# Sheet1.net
KiCad netlist of a schematic drawn in Altium Designer
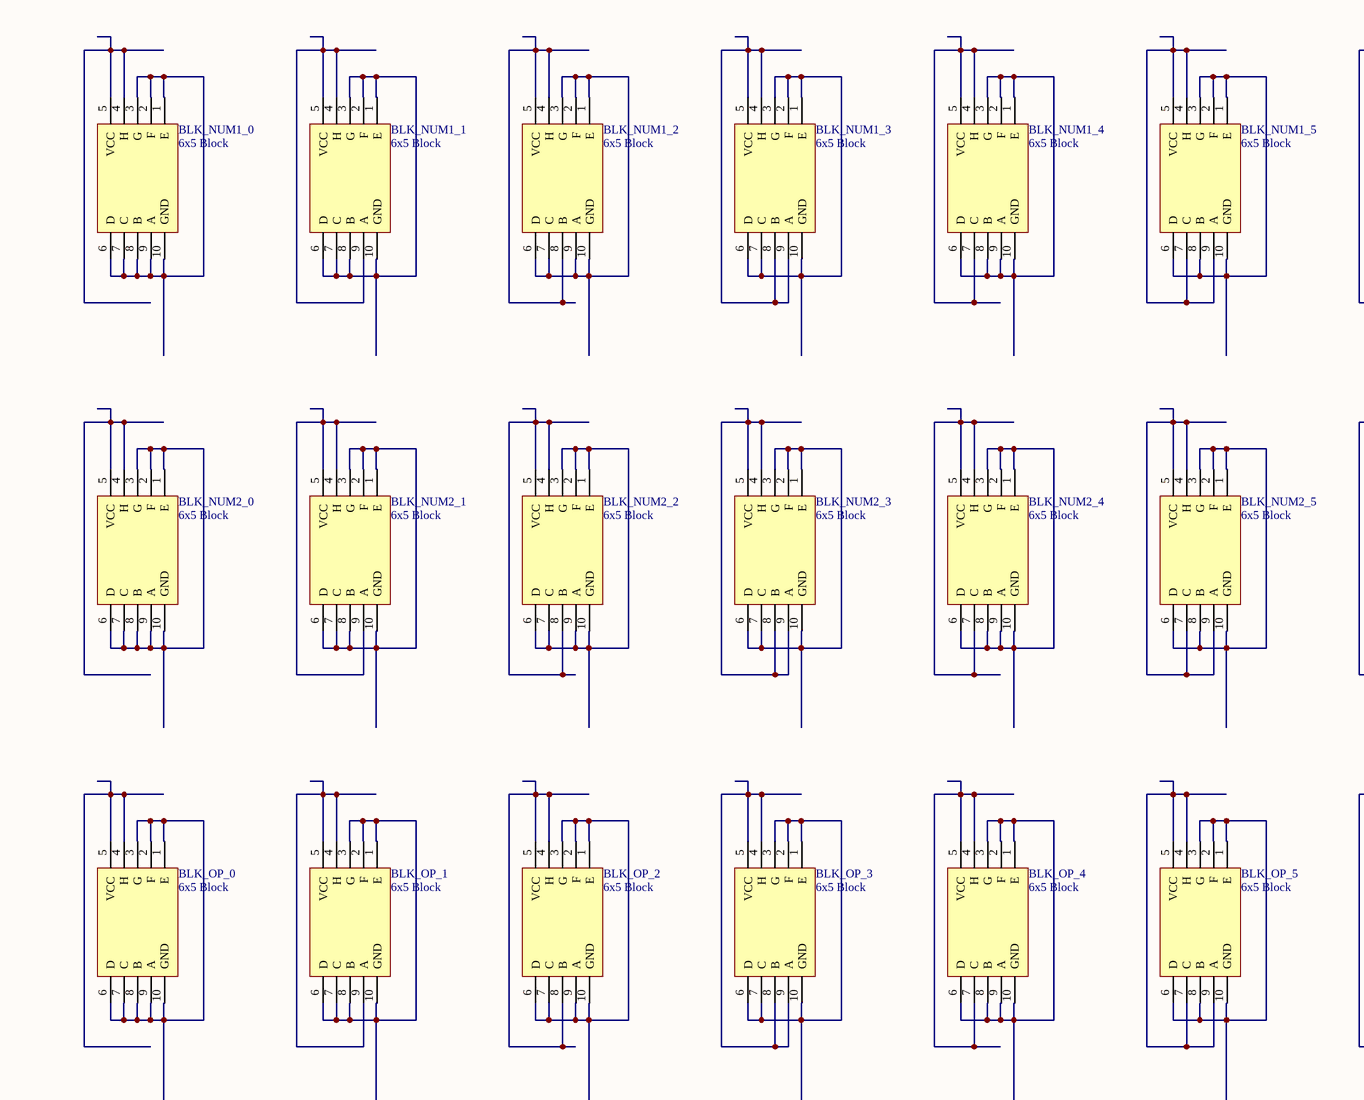
[diagram p0: Sheet1.SchDoc, left]
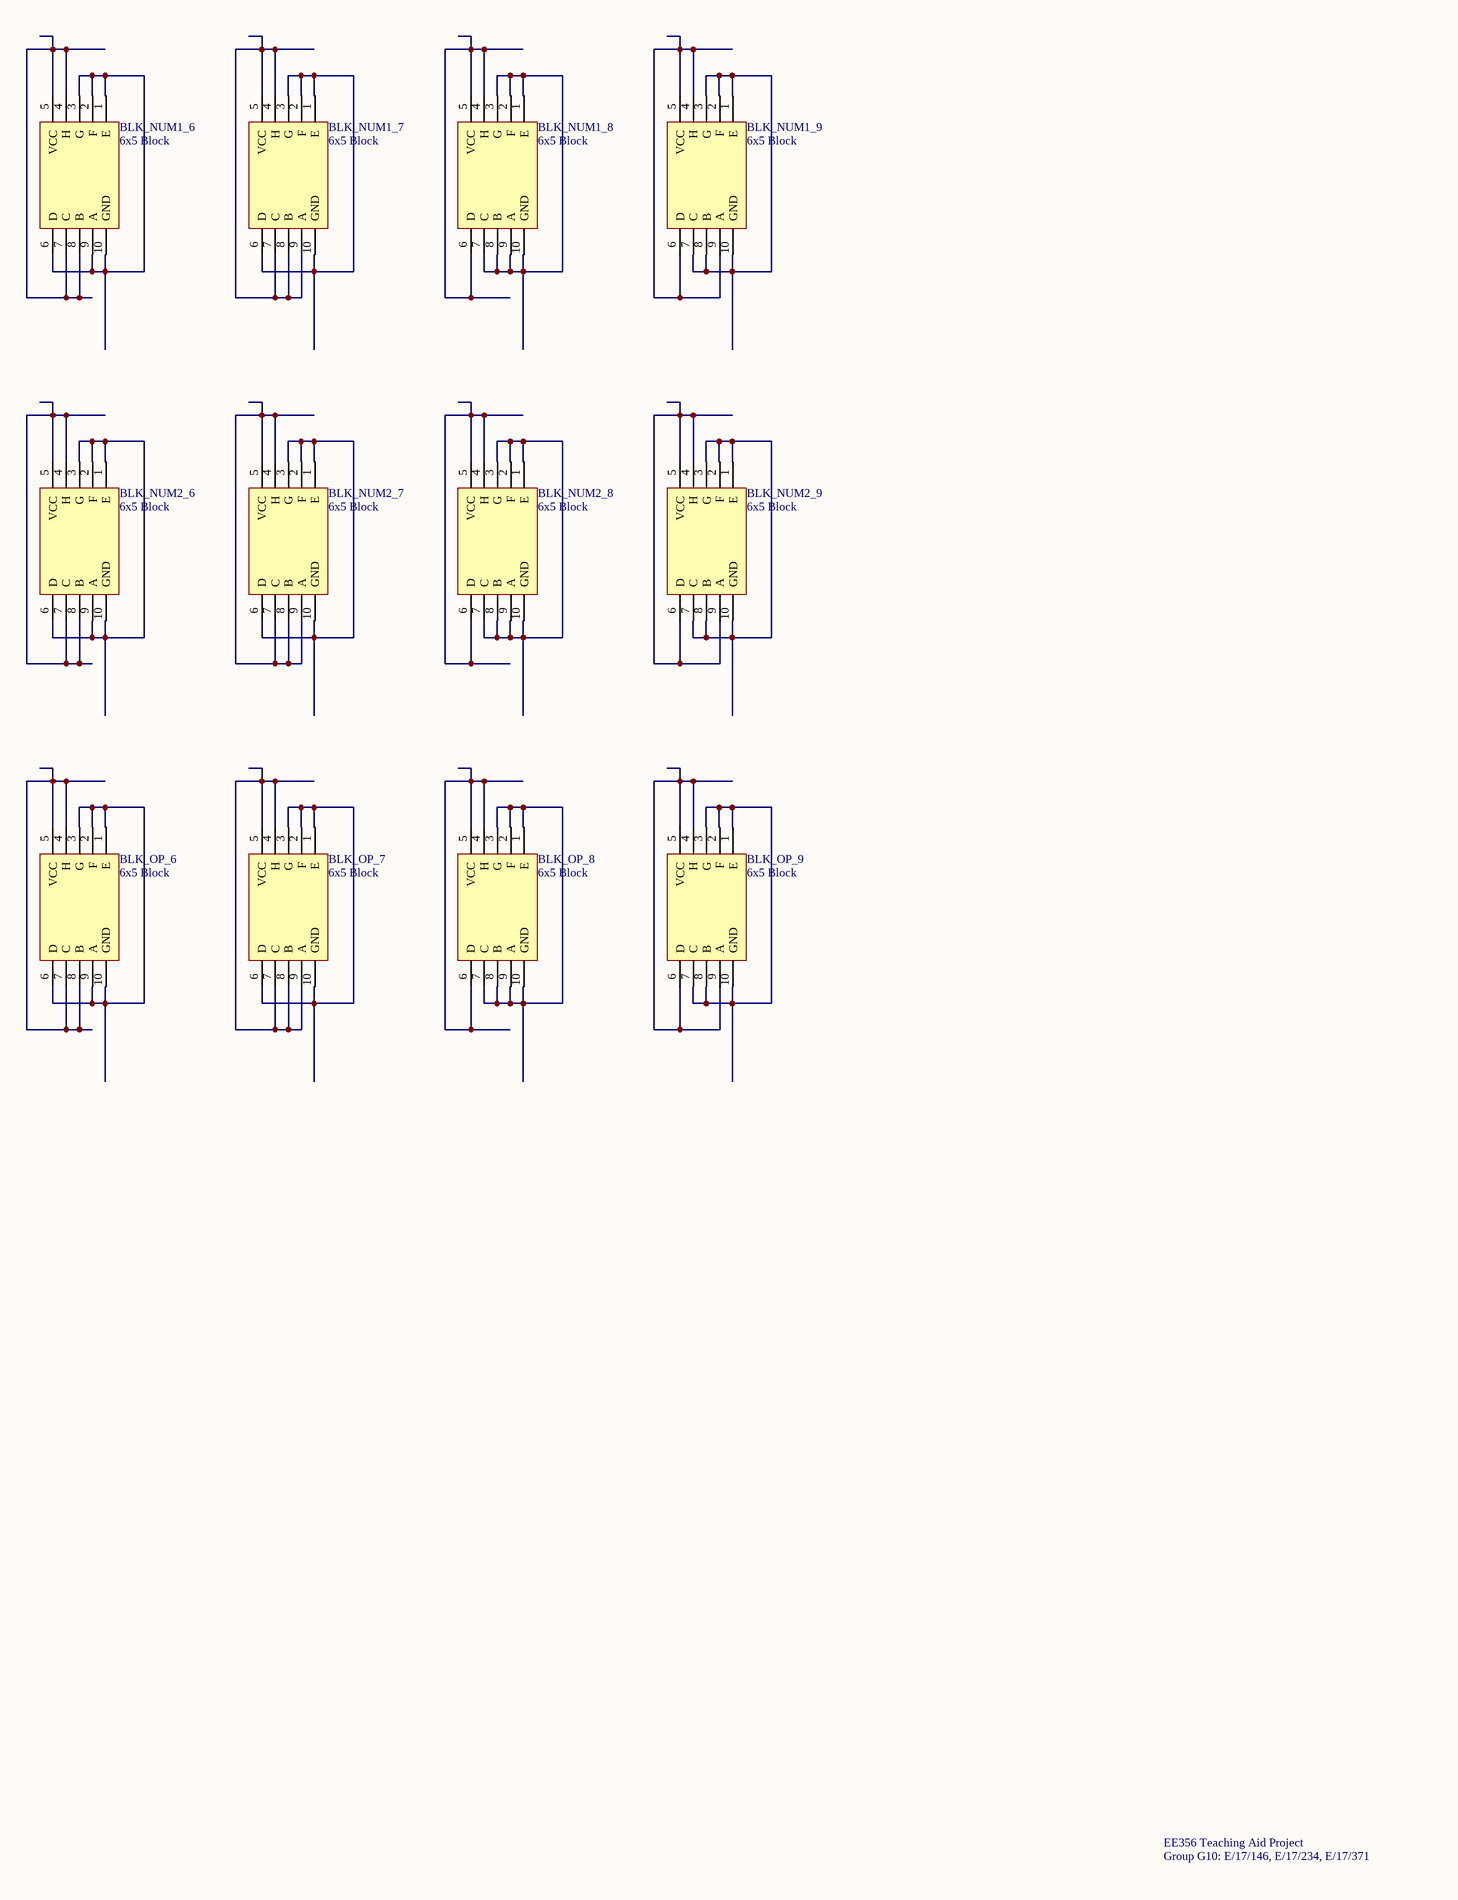
[diagram p1: Sheet1.SchDoc, right]

(export (version "E")
  (design (tool "Eeschema 10.0.6"))
  (components
    (comp (ref "BLK_NUM1_0")
      (value "6x5 Block")
      (footprint "Block_6x5")
      (libsource (lib "Schlib1") (part "Block_6x5"))
    )
    (comp (ref "BLK_NUM1_1")
      (value "6x5 Block")
      (footprint "Block_6x5")
      (libsource (lib "Schlib1") (part "Block_6x5"))
    )
    (comp (ref "BLK_NUM1_2")
      (value "6x5 Block")
      (footprint "Block_6x5")
      (libsource (lib "Schlib1") (part "Block_6x5"))
    )
    (comp (ref "BLK_NUM1_3")
      (value "6x5 Block")
      (footprint "Block_6x5")
      (libsource (lib "Schlib1") (part "Block_6x5"))
    )
    (comp (ref "BLK_NUM1_4")
      (value "6x5 Block")
      (footprint "Block_6x5")
      (libsource (lib "Schlib1") (part "Block_6x5"))
    )
    (comp (ref "BLK_NUM1_5")
      (value "6x5 Block")
      (footprint "Block_6x5")
      (libsource (lib "Schlib1") (part "Block_6x5"))
    )
    (comp (ref "BLK_NUM1_6")
      (value "6x5 Block")
      (footprint "Block_6x5")
      (libsource (lib "Schlib1") (part "Block_6x5"))
    )
    (comp (ref "BLK_NUM1_7")
      (value "6x5 Block")
      (footprint "Block_6x5")
      (libsource (lib "Schlib1") (part "Block_6x5"))
    )
    (comp (ref "BLK_NUM1_8")
      (value "6x5 Block")
      (footprint "Block_6x5")
      (libsource (lib "Schlib1") (part "Block_6x5"))
    )
    (comp (ref "BLK_NUM1_9")
      (value "6x5 Block")
      (footprint "Block_6x5")
      (libsource (lib "Schlib1") (part "Block_6x5"))
    )
    (comp (ref "BLK_NUM2_0")
      (value "6x5 Block")
      (footprint "Block_6x5")
      (libsource (lib "Schlib1") (part "Block_6x5"))
    )
    (comp (ref "BLK_NUM2_1")
      (value "6x5 Block")
      (footprint "Block_6x5")
      (libsource (lib "Schlib1") (part "Block_6x5"))
    )
    (comp (ref "BLK_NUM2_2")
      (value "6x5 Block")
      (footprint "Block_6x5")
      (libsource (lib "Schlib1") (part "Block_6x5"))
    )
    (comp (ref "BLK_NUM2_3")
      (value "6x5 Block")
      (footprint "Block_6x5")
      (libsource (lib "Schlib1") (part "Block_6x5"))
    )
    (comp (ref "BLK_NUM2_4")
      (value "6x5 Block")
      (footprint "Block_6x5")
      (libsource (lib "Schlib1") (part "Block_6x5"))
    )
    (comp (ref "BLK_NUM2_5")
      (value "6x5 Block")
      (footprint "Block_6x5")
      (libsource (lib "Schlib1") (part "Block_6x5"))
    )
    (comp (ref "BLK_NUM2_6")
      (value "6x5 Block")
      (footprint "Block_6x5")
      (libsource (lib "Schlib1") (part "Block_6x5"))
    )
    (comp (ref "BLK_NUM2_7")
      (value "6x5 Block")
      (footprint "Block_6x5")
      (libsource (lib "Schlib1") (part "Block_6x5"))
    )
    (comp (ref "BLK_NUM2_8")
      (value "6x5 Block")
      (footprint "Block_6x5")
      (libsource (lib "Schlib1") (part "Block_6x5"))
    )
    (comp (ref "BLK_NUM2_9")
      (value "6x5 Block")
      (footprint "Block_6x5")
      (libsource (lib "Schlib1") (part "Block_6x5"))
    )
    (comp (ref "BLK_OP_0")
      (value "6x5 Block")
      (footprint "Block_6x5")
      (libsource (lib "Schlib1") (part "Block_6x5"))
    )
    (comp (ref "BLK_OP_1")
      (value "6x5 Block")
      (footprint "Block_6x5")
      (libsource (lib "Schlib1") (part "Block_6x5"))
    )
    (comp (ref "BLK_OP_2")
      (value "6x5 Block")
      (footprint "Block_6x5")
      (libsource (lib "Schlib1") (part "Block_6x5"))
    )
    (comp (ref "BLK_OP_3")
      (value "6x5 Block")
      (footprint "Block_6x5")
      (libsource (lib "Schlib1") (part "Block_6x5"))
    )
    (comp (ref "BLK_OP_4")
      (value "6x5 Block")
      (footprint "Block_6x5")
      (libsource (lib "Schlib1") (part "Block_6x5"))
    )
    (comp (ref "BLK_OP_5")
      (value "6x5 Block")
      (footprint "Block_6x5")
      (libsource (lib "Schlib1") (part "Block_6x5"))
    )
    (comp (ref "BLK_OP_6")
      (value "6x5 Block")
      (footprint "Block_6x5")
      (libsource (lib "Schlib1") (part "Block_6x5"))
    )
    (comp (ref "BLK_OP_7")
      (value "6x5 Block")
      (footprint "Block_6x5")
      (libsource (lib "Schlib1") (part "Block_6x5"))
    )
    (comp (ref "BLK_OP_8")
      (value "6x5 Block")
      (footprint "Block_6x5")
      (libsource (lib "Schlib1") (part "Block_6x5"))
    )
    (comp (ref "BLK_OP_9")
      (value "6x5 Block")
      (footprint "Block_6x5")
      (libsource (lib "Schlib1") (part "Block_6x5"))
    )
  )
  (nets
    (net (code "1") (name "Net-(BLK_NUM1_0-A)") (class "Default")
      (node (ref "BLK_NUM1_0") (pin "1") (pinfunction "E_1") (pintype "passive"))
      (node (ref "BLK_NUM1_0") (pin "10") (pinfunction "GND_10") (pintype "passive"))
      (node (ref "BLK_NUM1_0") (pin "2") (pinfunction "F_2") (pintype "passive"))
      (node (ref "BLK_NUM1_0") (pin "3") (pinfunction "G_3") (pintype "passive"))
      (node (ref "BLK_NUM1_0") (pin "6") (pinfunction "D_6") (pintype "passive"))
      (node (ref "BLK_NUM1_0") (pin "7") (pinfunction "C_7") (pintype "passive"))
      (node (ref "BLK_NUM1_0") (pin "8") (pinfunction "B_8") (pintype "passive"))
      (node (ref "BLK_NUM1_0") (pin "9") (pinfunction "A_9") (pintype "passive"))
    )
    (net (code "2") (name "Net-(BLK_NUM1_0-H)") (class "Default")
      (node (ref "BLK_NUM1_0") (pin "4") (pinfunction "H_4") (pintype "passive"))
      (node (ref "BLK_NUM1_0") (pin "5") (pinfunction "VCC_5") (pintype "passive"))
    )
    (net (code "3") (name "Net-(BLK_NUM1_1-A)") (class "Default")
      (node (ref "BLK_NUM1_1") (pin "4") (pinfunction "H_4") (pintype "passive"))
      (node (ref "BLK_NUM1_1") (pin "5") (pinfunction "VCC_5") (pintype "passive"))
      (node (ref "BLK_NUM1_1") (pin "9") (pinfunction "A_9") (pintype "passive"))
    )
    (net (code "4") (name "Net-(BLK_NUM1_1-B)") (class "Default")
      (node (ref "BLK_NUM1_1") (pin "1") (pinfunction "E_1") (pintype "passive"))
      (node (ref "BLK_NUM1_1") (pin "10") (pinfunction "GND_10") (pintype "passive"))
      (node (ref "BLK_NUM1_1") (pin "2") (pinfunction "F_2") (pintype "passive"))
      (node (ref "BLK_NUM1_1") (pin "3") (pinfunction "G_3") (pintype "passive"))
      (node (ref "BLK_NUM1_1") (pin "6") (pinfunction "D_6") (pintype "passive"))
      (node (ref "BLK_NUM1_1") (pin "7") (pinfunction "C_7") (pintype "passive"))
      (node (ref "BLK_NUM1_1") (pin "8") (pinfunction "B_8") (pintype "passive"))
    )
    (net (code "5") (name "Net-(BLK_NUM1_2-A)") (class "Default")
      (node (ref "BLK_NUM1_2") (pin "1") (pinfunction "E_1") (pintype "passive"))
      (node (ref "BLK_NUM1_2") (pin "10") (pinfunction "GND_10") (pintype "passive"))
      (node (ref "BLK_NUM1_2") (pin "2") (pinfunction "F_2") (pintype "passive"))
      (node (ref "BLK_NUM1_2") (pin "3") (pinfunction "G_3") (pintype "passive"))
      (node (ref "BLK_NUM1_2") (pin "6") (pinfunction "D_6") (pintype "passive"))
      (node (ref "BLK_NUM1_2") (pin "7") (pinfunction "C_7") (pintype "passive"))
      (node (ref "BLK_NUM1_2") (pin "9") (pinfunction "A_9") (pintype "passive"))
    )
    (net (code "6") (name "Net-(BLK_NUM1_2-B)") (class "Default")
      (node (ref "BLK_NUM1_2") (pin "4") (pinfunction "H_4") (pintype "passive"))
      (node (ref "BLK_NUM1_2") (pin "5") (pinfunction "VCC_5") (pintype "passive"))
      (node (ref "BLK_NUM1_2") (pin "8") (pinfunction "B_8") (pintype "passive"))
    )
    (net (code "7") (name "Net-(BLK_NUM1_3-A)") (class "Default")
      (node (ref "BLK_NUM1_3") (pin "4") (pinfunction "H_4") (pintype "passive"))
      (node (ref "BLK_NUM1_3") (pin "5") (pinfunction "VCC_5") (pintype "passive"))
      (node (ref "BLK_NUM1_3") (pin "8") (pinfunction "B_8") (pintype "passive"))
      (node (ref "BLK_NUM1_3") (pin "9") (pinfunction "A_9") (pintype "passive"))
    )
    (net (code "8") (name "Net-(BLK_NUM1_3-C)") (class "Default")
      (node (ref "BLK_NUM1_3") (pin "1") (pinfunction "E_1") (pintype "passive"))
      (node (ref "BLK_NUM1_3") (pin "10") (pinfunction "GND_10") (pintype "passive"))
      (node (ref "BLK_NUM1_3") (pin "2") (pinfunction "F_2") (pintype "passive"))
      (node (ref "BLK_NUM1_3") (pin "3") (pinfunction "G_3") (pintype "passive"))
      (node (ref "BLK_NUM1_3") (pin "6") (pinfunction "D_6") (pintype "passive"))
      (node (ref "BLK_NUM1_3") (pin "7") (pinfunction "C_7") (pintype "passive"))
    )
    (net (code "9") (name "Net-(BLK_NUM1_4-A)") (class "Default")
      (node (ref "BLK_NUM1_4") (pin "1") (pinfunction "E_1") (pintype "passive"))
      (node (ref "BLK_NUM1_4") (pin "10") (pinfunction "GND_10") (pintype "passive"))
      (node (ref "BLK_NUM1_4") (pin "2") (pinfunction "F_2") (pintype "passive"))
      (node (ref "BLK_NUM1_4") (pin "3") (pinfunction "G_3") (pintype "passive"))
      (node (ref "BLK_NUM1_4") (pin "6") (pinfunction "D_6") (pintype "passive"))
      (node (ref "BLK_NUM1_4") (pin "8") (pinfunction "B_8") (pintype "passive"))
      (node (ref "BLK_NUM1_4") (pin "9") (pinfunction "A_9") (pintype "passive"))
    )
    (net (code "10") (name "Net-(BLK_NUM1_4-C)") (class "Default")
      (node (ref "BLK_NUM1_4") (pin "4") (pinfunction "H_4") (pintype "passive"))
      (node (ref "BLK_NUM1_4") (pin "5") (pinfunction "VCC_5") (pintype "passive"))
      (node (ref "BLK_NUM1_4") (pin "7") (pinfunction "C_7") (pintype "passive"))
    )
    (net (code "11") (name "Net-(BLK_NUM1_5-A)") (class "Default")
      (node (ref "BLK_NUM1_5") (pin "4") (pinfunction "H_4") (pintype "passive"))
      (node (ref "BLK_NUM1_5") (pin "5") (pinfunction "VCC_5") (pintype "passive"))
      (node (ref "BLK_NUM1_5") (pin "7") (pinfunction "C_7") (pintype "passive"))
      (node (ref "BLK_NUM1_5") (pin "9") (pinfunction "A_9") (pintype "passive"))
    )
    (net (code "12") (name "Net-(BLK_NUM1_5-B)") (class "Default")
      (node (ref "BLK_NUM1_5") (pin "1") (pinfunction "E_1") (pintype "passive"))
      (node (ref "BLK_NUM1_5") (pin "10") (pinfunction "GND_10") (pintype "passive"))
      (node (ref "BLK_NUM1_5") (pin "2") (pinfunction "F_2") (pintype "passive"))
      (node (ref "BLK_NUM1_5") (pin "3") (pinfunction "G_3") (pintype "passive"))
      (node (ref "BLK_NUM1_5") (pin "6") (pinfunction "D_6") (pintype "passive"))
      (node (ref "BLK_NUM1_5") (pin "8") (pinfunction "B_8") (pintype "passive"))
    )
    (net (code "13") (name "Net-(BLK_NUM1_6-A)") (class "Default")
      (node (ref "BLK_NUM1_6") (pin "1") (pinfunction "E_1") (pintype "passive"))
      (node (ref "BLK_NUM1_6") (pin "10") (pinfunction "GND_10") (pintype "passive"))
      (node (ref "BLK_NUM1_6") (pin "2") (pinfunction "F_2") (pintype "passive"))
      (node (ref "BLK_NUM1_6") (pin "3") (pinfunction "G_3") (pintype "passive"))
      (node (ref "BLK_NUM1_6") (pin "6") (pinfunction "D_6") (pintype "passive"))
      (node (ref "BLK_NUM1_6") (pin "9") (pinfunction "A_9") (pintype "passive"))
    )
    (net (code "14") (name "Net-(BLK_NUM1_6-B)") (class "Default")
      (node (ref "BLK_NUM1_6") (pin "4") (pinfunction "H_4") (pintype "passive"))
      (node (ref "BLK_NUM1_6") (pin "5") (pinfunction "VCC_5") (pintype "passive"))
      (node (ref "BLK_NUM1_6") (pin "7") (pinfunction "C_7") (pintype "passive"))
      (node (ref "BLK_NUM1_6") (pin "8") (pinfunction "B_8") (pintype "passive"))
    )
    (net (code "15") (name "Net-(BLK_NUM1_7-A)") (class "Default")
      (node (ref "BLK_NUM1_7") (pin "4") (pinfunction "H_4") (pintype "passive"))
      (node (ref "BLK_NUM1_7") (pin "5") (pinfunction "VCC_5") (pintype "passive"))
      (node (ref "BLK_NUM1_7") (pin "7") (pinfunction "C_7") (pintype "passive"))
      (node (ref "BLK_NUM1_7") (pin "8") (pinfunction "B_8") (pintype "passive"))
      (node (ref "BLK_NUM1_7") (pin "9") (pinfunction "A_9") (pintype "passive"))
    )
    (net (code "16") (name "Net-(BLK_NUM1_7-D)") (class "Default")
      (node (ref "BLK_NUM1_7") (pin "1") (pinfunction "E_1") (pintype "passive"))
      (node (ref "BLK_NUM1_7") (pin "10") (pinfunction "GND_10") (pintype "passive"))
      (node (ref "BLK_NUM1_7") (pin "2") (pinfunction "F_2") (pintype "passive"))
      (node (ref "BLK_NUM1_7") (pin "3") (pinfunction "G_3") (pintype "passive"))
      (node (ref "BLK_NUM1_7") (pin "6") (pinfunction "D_6") (pintype "passive"))
    )
    (net (code "17") (name "Net-(BLK_NUM1_8-A)") (class "Default")
      (node (ref "BLK_NUM1_8") (pin "1") (pinfunction "E_1") (pintype "passive"))
      (node (ref "BLK_NUM1_8") (pin "10") (pinfunction "GND_10") (pintype "passive"))
      (node (ref "BLK_NUM1_8") (pin "2") (pinfunction "F_2") (pintype "passive"))
      (node (ref "BLK_NUM1_8") (pin "3") (pinfunction "G_3") (pintype "passive"))
      (node (ref "BLK_NUM1_8") (pin "7") (pinfunction "C_7") (pintype "passive"))
      (node (ref "BLK_NUM1_8") (pin "8") (pinfunction "B_8") (pintype "passive"))
      (node (ref "BLK_NUM1_8") (pin "9") (pinfunction "A_9") (pintype "passive"))
    )
    (net (code "18") (name "Net-(BLK_NUM1_8-D)") (class "Default")
      (node (ref "BLK_NUM1_8") (pin "4") (pinfunction "H_4") (pintype "passive"))
      (node (ref "BLK_NUM1_8") (pin "5") (pinfunction "VCC_5") (pintype "passive"))
      (node (ref "BLK_NUM1_8") (pin "6") (pinfunction "D_6") (pintype "passive"))
    )
    (net (code "19") (name "Net-(BLK_NUM1_9-A)") (class "Default")
      (node (ref "BLK_NUM1_9") (pin "4") (pinfunction "H_4") (pintype "passive"))
      (node (ref "BLK_NUM1_9") (pin "5") (pinfunction "VCC_5") (pintype "passive"))
      (node (ref "BLK_NUM1_9") (pin "6") (pinfunction "D_6") (pintype "passive"))
      (node (ref "BLK_NUM1_9") (pin "9") (pinfunction "A_9") (pintype "passive"))
    )
    (net (code "20") (name "Net-(BLK_NUM1_9-B)") (class "Default")
      (node (ref "BLK_NUM1_9") (pin "1") (pinfunction "E_1") (pintype "passive"))
      (node (ref "BLK_NUM1_9") (pin "10") (pinfunction "GND_10") (pintype "passive"))
      (node (ref "BLK_NUM1_9") (pin "2") (pinfunction "F_2") (pintype "passive"))
      (node (ref "BLK_NUM1_9") (pin "3") (pinfunction "G_3") (pintype "passive"))
      (node (ref "BLK_NUM1_9") (pin "7") (pinfunction "C_7") (pintype "passive"))
      (node (ref "BLK_NUM1_9") (pin "8") (pinfunction "B_8") (pintype "passive"))
    )
    (net (code "21") (name "Net-(BLK_NUM2_0-A)") (class "Default")
      (node (ref "BLK_NUM2_0") (pin "1") (pinfunction "E_1") (pintype "passive"))
      (node (ref "BLK_NUM2_0") (pin "10") (pinfunction "GND_10") (pintype "passive"))
      (node (ref "BLK_NUM2_0") (pin "2") (pinfunction "F_2") (pintype "passive"))
      (node (ref "BLK_NUM2_0") (pin "3") (pinfunction "G_3") (pintype "passive"))
      (node (ref "BLK_NUM2_0") (pin "6") (pinfunction "D_6") (pintype "passive"))
      (node (ref "BLK_NUM2_0") (pin "7") (pinfunction "C_7") (pintype "passive"))
      (node (ref "BLK_NUM2_0") (pin "8") (pinfunction "B_8") (pintype "passive"))
      (node (ref "BLK_NUM2_0") (pin "9") (pinfunction "A_9") (pintype "passive"))
    )
    (net (code "22") (name "Net-(BLK_NUM2_0-H)") (class "Default")
      (node (ref "BLK_NUM2_0") (pin "4") (pinfunction "H_4") (pintype "passive"))
      (node (ref "BLK_NUM2_0") (pin "5") (pinfunction "VCC_5") (pintype "passive"))
    )
    (net (code "23") (name "Net-(BLK_NUM2_1-A)") (class "Default")
      (node (ref "BLK_NUM2_1") (pin "4") (pinfunction "H_4") (pintype "passive"))
      (node (ref "BLK_NUM2_1") (pin "5") (pinfunction "VCC_5") (pintype "passive"))
      (node (ref "BLK_NUM2_1") (pin "9") (pinfunction "A_9") (pintype "passive"))
    )
    (net (code "24") (name "Net-(BLK_NUM2_1-B)") (class "Default")
      (node (ref "BLK_NUM2_1") (pin "1") (pinfunction "E_1") (pintype "passive"))
      (node (ref "BLK_NUM2_1") (pin "10") (pinfunction "GND_10") (pintype "passive"))
      (node (ref "BLK_NUM2_1") (pin "2") (pinfunction "F_2") (pintype "passive"))
      (node (ref "BLK_NUM2_1") (pin "3") (pinfunction "G_3") (pintype "passive"))
      (node (ref "BLK_NUM2_1") (pin "6") (pinfunction "D_6") (pintype "passive"))
      (node (ref "BLK_NUM2_1") (pin "7") (pinfunction "C_7") (pintype "passive"))
      (node (ref "BLK_NUM2_1") (pin "8") (pinfunction "B_8") (pintype "passive"))
    )
    (net (code "25") (name "Net-(BLK_NUM2_2-A)") (class "Default")
      (node (ref "BLK_NUM2_2") (pin "1") (pinfunction "E_1") (pintype "passive"))
      (node (ref "BLK_NUM2_2") (pin "10") (pinfunction "GND_10") (pintype "passive"))
      (node (ref "BLK_NUM2_2") (pin "2") (pinfunction "F_2") (pintype "passive"))
      (node (ref "BLK_NUM2_2") (pin "3") (pinfunction "G_3") (pintype "passive"))
      (node (ref "BLK_NUM2_2") (pin "6") (pinfunction "D_6") (pintype "passive"))
      (node (ref "BLK_NUM2_2") (pin "7") (pinfunction "C_7") (pintype "passive"))
      (node (ref "BLK_NUM2_2") (pin "9") (pinfunction "A_9") (pintype "passive"))
    )
    (net (code "26") (name "Net-(BLK_NUM2_2-B)") (class "Default")
      (node (ref "BLK_NUM2_2") (pin "4") (pinfunction "H_4") (pintype "passive"))
      (node (ref "BLK_NUM2_2") (pin "5") (pinfunction "VCC_5") (pintype "passive"))
      (node (ref "BLK_NUM2_2") (pin "8") (pinfunction "B_8") (pintype "passive"))
    )
    (net (code "27") (name "Net-(BLK_NUM2_3-A)") (class "Default")
      (node (ref "BLK_NUM2_3") (pin "4") (pinfunction "H_4") (pintype "passive"))
      (node (ref "BLK_NUM2_3") (pin "5") (pinfunction "VCC_5") (pintype "passive"))
      (node (ref "BLK_NUM2_3") (pin "8") (pinfunction "B_8") (pintype "passive"))
      (node (ref "BLK_NUM2_3") (pin "9") (pinfunction "A_9") (pintype "passive"))
    )
    (net (code "28") (name "Net-(BLK_NUM2_3-C)") (class "Default")
      (node (ref "BLK_NUM2_3") (pin "1") (pinfunction "E_1") (pintype "passive"))
      (node (ref "BLK_NUM2_3") (pin "10") (pinfunction "GND_10") (pintype "passive"))
      (node (ref "BLK_NUM2_3") (pin "2") (pinfunction "F_2") (pintype "passive"))
      (node (ref "BLK_NUM2_3") (pin "3") (pinfunction "G_3") (pintype "passive"))
      (node (ref "BLK_NUM2_3") (pin "6") (pinfunction "D_6") (pintype "passive"))
      (node (ref "BLK_NUM2_3") (pin "7") (pinfunction "C_7") (pintype "passive"))
    )
    (net (code "29") (name "Net-(BLK_NUM2_4-A)") (class "Default")
      (node (ref "BLK_NUM2_4") (pin "1") (pinfunction "E_1") (pintype "passive"))
      (node (ref "BLK_NUM2_4") (pin "10") (pinfunction "GND_10") (pintype "passive"))
      (node (ref "BLK_NUM2_4") (pin "2") (pinfunction "F_2") (pintype "passive"))
      (node (ref "BLK_NUM2_4") (pin "3") (pinfunction "G_3") (pintype "passive"))
      (node (ref "BLK_NUM2_4") (pin "6") (pinfunction "D_6") (pintype "passive"))
      (node (ref "BLK_NUM2_4") (pin "8") (pinfunction "B_8") (pintype "passive"))
      (node (ref "BLK_NUM2_4") (pin "9") (pinfunction "A_9") (pintype "passive"))
    )
    (net (code "30") (name "Net-(BLK_NUM2_4-C)") (class "Default")
      (node (ref "BLK_NUM2_4") (pin "4") (pinfunction "H_4") (pintype "passive"))
      (node (ref "BLK_NUM2_4") (pin "5") (pinfunction "VCC_5") (pintype "passive"))
      (node (ref "BLK_NUM2_4") (pin "7") (pinfunction "C_7") (pintype "passive"))
    )
    (net (code "31") (name "Net-(BLK_NUM2_5-A)") (class "Default")
      (node (ref "BLK_NUM2_5") (pin "4") (pinfunction "H_4") (pintype "passive"))
      (node (ref "BLK_NUM2_5") (pin "5") (pinfunction "VCC_5") (pintype "passive"))
      (node (ref "BLK_NUM2_5") (pin "7") (pinfunction "C_7") (pintype "passive"))
      (node (ref "BLK_NUM2_5") (pin "9") (pinfunction "A_9") (pintype "passive"))
    )
    (net (code "32") (name "Net-(BLK_NUM2_5-B)") (class "Default")
      (node (ref "BLK_NUM2_5") (pin "1") (pinfunction "E_1") (pintype "passive"))
      (node (ref "BLK_NUM2_5") (pin "10") (pinfunction "GND_10") (pintype "passive"))
      (node (ref "BLK_NUM2_5") (pin "2") (pinfunction "F_2") (pintype "passive"))
      (node (ref "BLK_NUM2_5") (pin "3") (pinfunction "G_3") (pintype "passive"))
      (node (ref "BLK_NUM2_5") (pin "6") (pinfunction "D_6") (pintype "passive"))
      (node (ref "BLK_NUM2_5") (pin "8") (pinfunction "B_8") (pintype "passive"))
    )
    (net (code "33") (name "Net-(BLK_NUM2_6-A)") (class "Default")
      (node (ref "BLK_NUM2_6") (pin "1") (pinfunction "E_1") (pintype "passive"))
      (node (ref "BLK_NUM2_6") (pin "10") (pinfunction "GND_10") (pintype "passive"))
      (node (ref "BLK_NUM2_6") (pin "2") (pinfunction "F_2") (pintype "passive"))
      (node (ref "BLK_NUM2_6") (pin "3") (pinfunction "G_3") (pintype "passive"))
      (node (ref "BLK_NUM2_6") (pin "6") (pinfunction "D_6") (pintype "passive"))
      (node (ref "BLK_NUM2_6") (pin "9") (pinfunction "A_9") (pintype "passive"))
    )
    (net (code "34") (name "Net-(BLK_NUM2_6-B)") (class "Default")
      (node (ref "BLK_NUM2_6") (pin "4") (pinfunction "H_4") (pintype "passive"))
      (node (ref "BLK_NUM2_6") (pin "5") (pinfunction "VCC_5") (pintype "passive"))
      (node (ref "BLK_NUM2_6") (pin "7") (pinfunction "C_7") (pintype "passive"))
      (node (ref "BLK_NUM2_6") (pin "8") (pinfunction "B_8") (pintype "passive"))
    )
    (net (code "35") (name "Net-(BLK_NUM2_7-A)") (class "Default")
      (node (ref "BLK_NUM2_7") (pin "4") (pinfunction "H_4") (pintype "passive"))
      (node (ref "BLK_NUM2_7") (pin "5") (pinfunction "VCC_5") (pintype "passive"))
      (node (ref "BLK_NUM2_7") (pin "7") (pinfunction "C_7") (pintype "passive"))
      (node (ref "BLK_NUM2_7") (pin "8") (pinfunction "B_8") (pintype "passive"))
      (node (ref "BLK_NUM2_7") (pin "9") (pinfunction "A_9") (pintype "passive"))
    )
    (net (code "36") (name "Net-(BLK_NUM2_7-D)") (class "Default")
      (node (ref "BLK_NUM2_7") (pin "1") (pinfunction "E_1") (pintype "passive"))
      (node (ref "BLK_NUM2_7") (pin "10") (pinfunction "GND_10") (pintype "passive"))
      (node (ref "BLK_NUM2_7") (pin "2") (pinfunction "F_2") (pintype "passive"))
      (node (ref "BLK_NUM2_7") (pin "3") (pinfunction "G_3") (pintype "passive"))
      (node (ref "BLK_NUM2_7") (pin "6") (pinfunction "D_6") (pintype "passive"))
    )
    (net (code "37") (name "Net-(BLK_NUM2_8-A)") (class "Default")
      (node (ref "BLK_NUM2_8") (pin "1") (pinfunction "E_1") (pintype "passive"))
      (node (ref "BLK_NUM2_8") (pin "10") (pinfunction "GND_10") (pintype "passive"))
      (node (ref "BLK_NUM2_8") (pin "2") (pinfunction "F_2") (pintype "passive"))
      (node (ref "BLK_NUM2_8") (pin "3") (pinfunction "G_3") (pintype "passive"))
      (node (ref "BLK_NUM2_8") (pin "7") (pinfunction "C_7") (pintype "passive"))
      (node (ref "BLK_NUM2_8") (pin "8") (pinfunction "B_8") (pintype "passive"))
      (node (ref "BLK_NUM2_8") (pin "9") (pinfunction "A_9") (pintype "passive"))
    )
    (net (code "38") (name "Net-(BLK_NUM2_8-D)") (class "Default")
      (node (ref "BLK_NUM2_8") (pin "4") (pinfunction "H_4") (pintype "passive"))
      (node (ref "BLK_NUM2_8") (pin "5") (pinfunction "VCC_5") (pintype "passive"))
      (node (ref "BLK_NUM2_8") (pin "6") (pinfunction "D_6") (pintype "passive"))
    )
    (net (code "39") (name "Net-(BLK_NUM2_9-A)") (class "Default")
      (node (ref "BLK_NUM2_9") (pin "4") (pinfunction "H_4") (pintype "passive"))
      (node (ref "BLK_NUM2_9") (pin "5") (pinfunction "VCC_5") (pintype "passive"))
      (node (ref "BLK_NUM2_9") (pin "6") (pinfunction "D_6") (pintype "passive"))
      (node (ref "BLK_NUM2_9") (pin "9") (pinfunction "A_9") (pintype "passive"))
    )
    (net (code "40") (name "Net-(BLK_NUM2_9-B)") (class "Default")
      (node (ref "BLK_NUM2_9") (pin "1") (pinfunction "E_1") (pintype "passive"))
      (node (ref "BLK_NUM2_9") (pin "10") (pinfunction "GND_10") (pintype "passive"))
      (node (ref "BLK_NUM2_9") (pin "2") (pinfunction "F_2") (pintype "passive"))
      (node (ref "BLK_NUM2_9") (pin "3") (pinfunction "G_3") (pintype "passive"))
      (node (ref "BLK_NUM2_9") (pin "7") (pinfunction "C_7") (pintype "passive"))
      (node (ref "BLK_NUM2_9") (pin "8") (pinfunction "B_8") (pintype "passive"))
    )
    (net (code "41") (name "Net-(BLK_OP_0-A)") (class "Default")
      (node (ref "BLK_OP_0") (pin "1") (pinfunction "E_1") (pintype "passive"))
      (node (ref "BLK_OP_0") (pin "10") (pinfunction "GND_10") (pintype "passive"))
      (node (ref "BLK_OP_0") (pin "2") (pinfunction "F_2") (pintype "passive"))
      (node (ref "BLK_OP_0") (pin "3") (pinfunction "G_3") (pintype "passive"))
      (node (ref "BLK_OP_0") (pin "6") (pinfunction "D_6") (pintype "passive"))
      (node (ref "BLK_OP_0") (pin "7") (pinfunction "C_7") (pintype "passive"))
      (node (ref "BLK_OP_0") (pin "8") (pinfunction "B_8") (pintype "passive"))
      (node (ref "BLK_OP_0") (pin "9") (pinfunction "A_9") (pintype "passive"))
    )
    (net (code "42") (name "Net-(BLK_OP_0-H)") (class "Default")
      (node (ref "BLK_OP_0") (pin "4") (pinfunction "H_4") (pintype "passive"))
      (node (ref "BLK_OP_0") (pin "5") (pinfunction "VCC_5") (pintype "passive"))
    )
    (net (code "43") (name "Net-(BLK_OP_1-A)") (class "Default")
      (node (ref "BLK_OP_1") (pin "4") (pinfunction "H_4") (pintype "passive"))
      (node (ref "BLK_OP_1") (pin "5") (pinfunction "VCC_5") (pintype "passive"))
      (node (ref "BLK_OP_1") (pin "9") (pinfunction "A_9") (pintype "passive"))
    )
    (net (code "44") (name "Net-(BLK_OP_1-B)") (class "Default")
      (node (ref "BLK_OP_1") (pin "1") (pinfunction "E_1") (pintype "passive"))
      (node (ref "BLK_OP_1") (pin "10") (pinfunction "GND_10") (pintype "passive"))
      (node (ref "BLK_OP_1") (pin "2") (pinfunction "F_2") (pintype "passive"))
      (node (ref "BLK_OP_1") (pin "3") (pinfunction "G_3") (pintype "passive"))
      (node (ref "BLK_OP_1") (pin "6") (pinfunction "D_6") (pintype "passive"))
      (node (ref "BLK_OP_1") (pin "7") (pinfunction "C_7") (pintype "passive"))
      (node (ref "BLK_OP_1") (pin "8") (pinfunction "B_8") (pintype "passive"))
    )
    (net (code "45") (name "Net-(BLK_OP_2-A)") (class "Default")
      (node (ref "BLK_OP_2") (pin "1") (pinfunction "E_1") (pintype "passive"))
      (node (ref "BLK_OP_2") (pin "10") (pinfunction "GND_10") (pintype "passive"))
      (node (ref "BLK_OP_2") (pin "2") (pinfunction "F_2") (pintype "passive"))
      (node (ref "BLK_OP_2") (pin "3") (pinfunction "G_3") (pintype "passive"))
      (node (ref "BLK_OP_2") (pin "6") (pinfunction "D_6") (pintype "passive"))
      (node (ref "BLK_OP_2") (pin "7") (pinfunction "C_7") (pintype "passive"))
      (node (ref "BLK_OP_2") (pin "9") (pinfunction "A_9") (pintype "passive"))
    )
    (net (code "46") (name "Net-(BLK_OP_2-B)") (class "Default")
      (node (ref "BLK_OP_2") (pin "4") (pinfunction "H_4") (pintype "passive"))
      (node (ref "BLK_OP_2") (pin "5") (pinfunction "VCC_5") (pintype "passive"))
      (node (ref "BLK_OP_2") (pin "8") (pinfunction "B_8") (pintype "passive"))
    )
    (net (code "47") (name "Net-(BLK_OP_3-A)") (class "Default")
      (node (ref "BLK_OP_3") (pin "4") (pinfunction "H_4") (pintype "passive"))
      (node (ref "BLK_OP_3") (pin "5") (pinfunction "VCC_5") (pintype "passive"))
      (node (ref "BLK_OP_3") (pin "8") (pinfunction "B_8") (pintype "passive"))
      (node (ref "BLK_OP_3") (pin "9") (pinfunction "A_9") (pintype "passive"))
    )
    (net (code "48") (name "Net-(BLK_OP_3-C)") (class "Default")
      (node (ref "BLK_OP_3") (pin "1") (pinfunction "E_1") (pintype "passive"))
      (node (ref "BLK_OP_3") (pin "10") (pinfunction "GND_10") (pintype "passive"))
      (node (ref "BLK_OP_3") (pin "2") (pinfunction "F_2") (pintype "passive"))
      (node (ref "BLK_OP_3") (pin "3") (pinfunction "G_3") (pintype "passive"))
      (node (ref "BLK_OP_3") (pin "6") (pinfunction "D_6") (pintype "passive"))
      (node (ref "BLK_OP_3") (pin "7") (pinfunction "C_7") (pintype "passive"))
    )
    (net (code "49") (name "Net-(BLK_OP_4-A)") (class "Default")
      (node (ref "BLK_OP_4") (pin "1") (pinfunction "E_1") (pintype "passive"))
      (node (ref "BLK_OP_4") (pin "10") (pinfunction "GND_10") (pintype "passive"))
      (node (ref "BLK_OP_4") (pin "2") (pinfunction "F_2") (pintype "passive"))
      (node (ref "BLK_OP_4") (pin "3") (pinfunction "G_3") (pintype "passive"))
      (node (ref "BLK_OP_4") (pin "6") (pinfunction "D_6") (pintype "passive"))
      (node (ref "BLK_OP_4") (pin "8") (pinfunction "B_8") (pintype "passive"))
      (node (ref "BLK_OP_4") (pin "9") (pinfunction "A_9") (pintype "passive"))
    )
    (net (code "50") (name "Net-(BLK_OP_4-C)") (class "Default")
      (node (ref "BLK_OP_4") (pin "4") (pinfunction "H_4") (pintype "passive"))
      (node (ref "BLK_OP_4") (pin "5") (pinfunction "VCC_5") (pintype "passive"))
      (node (ref "BLK_OP_4") (pin "7") (pinfunction "C_7") (pintype "passive"))
    )
    (net (code "51") (name "Net-(BLK_OP_5-A)") (class "Default")
      (node (ref "BLK_OP_5") (pin "4") (pinfunction "H_4") (pintype "passive"))
      (node (ref "BLK_OP_5") (pin "5") (pinfunction "VCC_5") (pintype "passive"))
      (node (ref "BLK_OP_5") (pin "7") (pinfunction "C_7") (pintype "passive"))
      (node (ref "BLK_OP_5") (pin "9") (pinfunction "A_9") (pintype "passive"))
    )
    (net (code "52") (name "Net-(BLK_OP_5-B)") (class "Default")
      (node (ref "BLK_OP_5") (pin "1") (pinfunction "E_1") (pintype "passive"))
      (node (ref "BLK_OP_5") (pin "10") (pinfunction "GND_10") (pintype "passive"))
      (node (ref "BLK_OP_5") (pin "2") (pinfunction "F_2") (pintype "passive"))
      (node (ref "BLK_OP_5") (pin "3") (pinfunction "G_3") (pintype "passive"))
      (node (ref "BLK_OP_5") (pin "6") (pinfunction "D_6") (pintype "passive"))
      (node (ref "BLK_OP_5") (pin "8") (pinfunction "B_8") (pintype "passive"))
    )
    (net (code "53") (name "Net-(BLK_OP_6-A)") (class "Default")
      (node (ref "BLK_OP_6") (pin "1") (pinfunction "E_1") (pintype "passive"))
      (node (ref "BLK_OP_6") (pin "10") (pinfunction "GND_10") (pintype "passive"))
      (node (ref "BLK_OP_6") (pin "2") (pinfunction "F_2") (pintype "passive"))
      (node (ref "BLK_OP_6") (pin "3") (pinfunction "G_3") (pintype "passive"))
      (node (ref "BLK_OP_6") (pin "6") (pinfunction "D_6") (pintype "passive"))
      (node (ref "BLK_OP_6") (pin "9") (pinfunction "A_9") (pintype "passive"))
    )
    (net (code "54") (name "Net-(BLK_OP_6-B)") (class "Default")
      (node (ref "BLK_OP_6") (pin "4") (pinfunction "H_4") (pintype "passive"))
      (node (ref "BLK_OP_6") (pin "5") (pinfunction "VCC_5") (pintype "passive"))
      (node (ref "BLK_OP_6") (pin "7") (pinfunction "C_7") (pintype "passive"))
      (node (ref "BLK_OP_6") (pin "8") (pinfunction "B_8") (pintype "passive"))
    )
    (net (code "55") (name "Net-(BLK_OP_7-A)") (class "Default")
      (node (ref "BLK_OP_7") (pin "4") (pinfunction "H_4") (pintype "passive"))
      (node (ref "BLK_OP_7") (pin "5") (pinfunction "VCC_5") (pintype "passive"))
      (node (ref "BLK_OP_7") (pin "7") (pinfunction "C_7") (pintype "passive"))
      (node (ref "BLK_OP_7") (pin "8") (pinfunction "B_8") (pintype "passive"))
      (node (ref "BLK_OP_7") (pin "9") (pinfunction "A_9") (pintype "passive"))
    )
    (net (code "56") (name "Net-(BLK_OP_7-D)") (class "Default")
      (node (ref "BLK_OP_7") (pin "1") (pinfunction "E_1") (pintype "passive"))
      (node (ref "BLK_OP_7") (pin "10") (pinfunction "GND_10") (pintype "passive"))
      (node (ref "BLK_OP_7") (pin "2") (pinfunction "F_2") (pintype "passive"))
      (node (ref "BLK_OP_7") (pin "3") (pinfunction "G_3") (pintype "passive"))
      (node (ref "BLK_OP_7") (pin "6") (pinfunction "D_6") (pintype "passive"))
    )
    (net (code "57") (name "Net-(BLK_OP_8-A)") (class "Default")
      (node (ref "BLK_OP_8") (pin "1") (pinfunction "E_1") (pintype "passive"))
      (node (ref "BLK_OP_8") (pin "10") (pinfunction "GND_10") (pintype "passive"))
      (node (ref "BLK_OP_8") (pin "2") (pinfunction "F_2") (pintype "passive"))
      (node (ref "BLK_OP_8") (pin "3") (pinfunction "G_3") (pintype "passive"))
      (node (ref "BLK_OP_8") (pin "7") (pinfunction "C_7") (pintype "passive"))
      (node (ref "BLK_OP_8") (pin "8") (pinfunction "B_8") (pintype "passive"))
      (node (ref "BLK_OP_8") (pin "9") (pinfunction "A_9") (pintype "passive"))
    )
    (net (code "58") (name "Net-(BLK_OP_8-D)") (class "Default")
      (node (ref "BLK_OP_8") (pin "4") (pinfunction "H_4") (pintype "passive"))
      (node (ref "BLK_OP_8") (pin "5") (pinfunction "VCC_5") (pintype "passive"))
      (node (ref "BLK_OP_8") (pin "6") (pinfunction "D_6") (pintype "passive"))
    )
    (net (code "59") (name "Net-(BLK_OP_9-A)") (class "Default")
      (node (ref "BLK_OP_9") (pin "4") (pinfunction "H_4") (pintype "passive"))
      (node (ref "BLK_OP_9") (pin "5") (pinfunction "VCC_5") (pintype "passive"))
      (node (ref "BLK_OP_9") (pin "6") (pinfunction "D_6") (pintype "passive"))
      (node (ref "BLK_OP_9") (pin "9") (pinfunction "A_9") (pintype "passive"))
    )
    (net (code "60") (name "Net-(BLK_OP_9-B)") (class "Default")
      (node (ref "BLK_OP_9") (pin "1") (pinfunction "E_1") (pintype "passive"))
      (node (ref "BLK_OP_9") (pin "10") (pinfunction "GND_10") (pintype "passive"))
      (node (ref "BLK_OP_9") (pin "2") (pinfunction "F_2") (pintype "passive"))
      (node (ref "BLK_OP_9") (pin "3") (pinfunction "G_3") (pintype "passive"))
      (node (ref "BLK_OP_9") (pin "7") (pinfunction "C_7") (pintype "passive"))
      (node (ref "BLK_OP_9") (pin "8") (pinfunction "B_8") (pintype "passive"))
    )
  )
)
